# 3-pin-radio-programmer.net
KiCad netlist of a schematic drawn in EAGLE
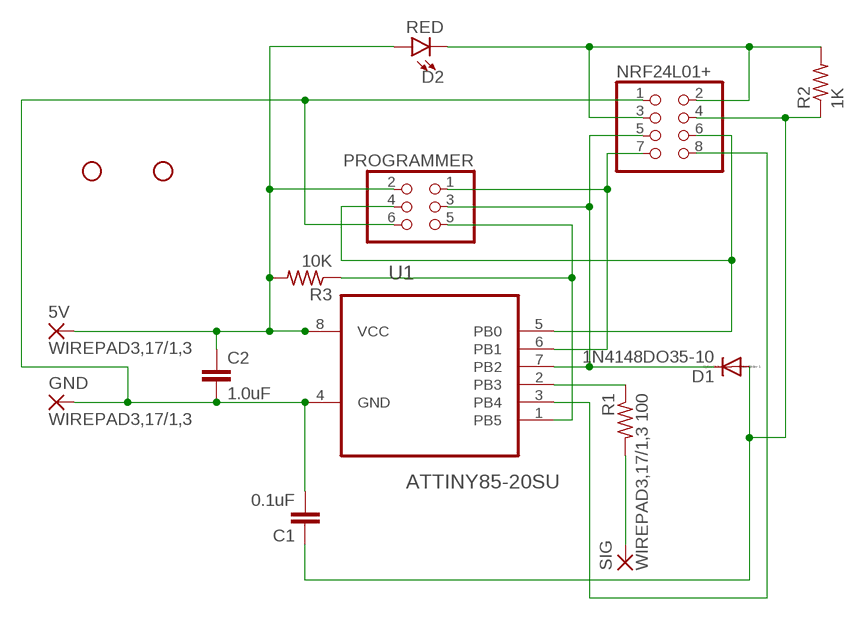
[diagram p0: schematic, sheet 1]

(export (version "E")
  (design (tool "Eeschema 10.0.6"))
  (components
    (comp (ref "5V")
      (value "WIREPAD3,17/1,3")
      (footprint "eagle-import:3,17_1,3")
      (libsource (lib "eagle-import") (part "WIREPAD3,17/1,3"))
    )
    (comp (ref "C1")
      (value "0.1uF")
      (footprint "eagle-import:0603")
      (libsource (lib "eagle-import") (part "0.1UF-0603-25V-5%"))
    )
    (comp (ref "C2")
      (value "1.0uF")
      (footprint "eagle-import:0603")
      (libsource (lib "eagle-import") (part "1.0UF-0603-16V-10%"))
    )
    (comp (ref "D1")
      (value "1N4148DO35-10")
      (footprint "eagle-import:DO35-10")
      (libsource (lib "eagle-import") (part "1N4148DO35-10"))
    )
    (comp (ref "D2")
      (value "RED")
      (footprint "eagle-import:LED_3MM")
      (libsource (lib "eagle-import") (part "LED3MM"))
    )
    (comp (ref "GND")
      (value "WIREPAD3,17/1,3")
      (footprint "eagle-import:3,17_1,3")
      (libsource (lib "eagle-import") (part "WIREPAD3,17/1,3"))
    )
    (comp (ref "H1")
      (value "STAND-OFF")
      (footprint "eagle-import:STAND-OFF")
      (libsource (lib "eagle-import") (part "STAND-OFF"))
    )
    (comp (ref "H2")
      (value "STAND-OFF")
      (footprint "eagle-import:STAND-OFF")
      (libsource (lib "eagle-import") (part "STAND-OFF"))
    )
    (comp (ref "NRF24L01+")
      (value "PINHD-2X4")
      (footprint "eagle-import:2X04")
      (libsource (lib "eagle-import") (part "PINHD-2X4"))
    )
    (comp (ref "PROGRAMMER")
      (value "PINHD-2X3")
      (footprint "eagle-import:2X03")
      (libsource (lib "eagle-import") (part "PINHD-2X3"))
    )
    (comp (ref "R1")
      (value "100")
      (footprint "eagle-import:R0805")
      (libsource (lib "eagle-import") (part "R-US_R0805"))
    )
    (comp (ref "R2")
      (value "1K")
      (footprint "eagle-import:R0805")
      (libsource (lib "eagle-import") (part "R-US_R0805"))
    )
    (comp (ref "R3")
      (value "10K")
      (footprint "eagle-import:R0805")
      (libsource (lib "eagle-import") (part "R-US_R0805"))
    )
    (comp (ref "SIG")
      (value "WIREPAD3,17/1,3")
      (footprint "eagle-import:3,17_1,3")
      (libsource (lib "eagle-import") (part "WIREPAD3,17/1,3"))
    )
    (comp (ref "U1")
      (value "ATTINY85-20SU")
      (footprint "eagle-import:SOIC127P798X216-8N")
      (libsource (lib "eagle-import") (part "ATTINY85-20SU"))
    )
  )
  (nets
    (net (code "1") (name "Net-(5V-P)") (class "Default")
      (node (ref "5V") (pin "1") (pinfunction "P_1") (pintype "passive"))
      (node (ref "C2") (pin "1") (pinfunction "1_1") (pintype "passive"))
      (node (ref "D2") (pin "A") (pinfunction "A_A") (pintype "passive"))
      (node (ref "PROGRAMMER") (pin "2") (pinfunction "2_2") (pintype "passive"))
      (node (ref "R3") (pin "2") (pinfunction "2_2") (pintype "passive"))
      (node (ref "U1") (pin "8") (pinfunction "VCC_8") (pintype "power_in"))
    )
    (net (code "2") (name "Net-(C1-Pad1)") (class "Default")
      (node (ref "C1") (pin "1") (pinfunction "1_1") (pintype "passive"))
      (node (ref "D1") (pin "A") (pinfunction "A_A") (pintype "passive"))
      (node (ref "NRF24L01+") (pin "4") (pinfunction "4_4") (pintype "passive"))
      (node (ref "R2") (pin "1") (pinfunction "1_1") (pintype "passive"))
    )
    (net (code "3") (name "Net-(D2-C)") (class "Default")
      (node (ref "D2") (pin "K") (pinfunction "C_K") (pintype "passive"))
      (node (ref "NRF24L01+") (pin "2") (pinfunction "2_2") (pintype "passive"))
      (node (ref "NRF24L01+") (pin "3") (pinfunction "3_3") (pintype "passive"))
      (node (ref "R2") (pin "2") (pinfunction "2_2") (pintype "passive"))
    )
    (net (code "4") (name "Net-(GND-P)") (class "Default")
      (node (ref "C1") (pin "2") (pinfunction "2_2") (pintype "passive"))
      (node (ref "C2") (pin "2") (pinfunction "2_2") (pintype "passive"))
      (node (ref "GND") (pin "1") (pinfunction "P_1") (pintype "passive"))
      (node (ref "NRF24L01+") (pin "1") (pinfunction "1_1") (pintype "passive"))
      (node (ref "PROGRAMMER") (pin "6") (pinfunction "6_6") (pintype "passive"))
      (node (ref "U1") (pin "4") (pinfunction "GND_4") (pintype "passive"))
    )
    (net (code "5") (name "Net-(SIG-P)") (class "Default")
      (node (ref "R1") (pin "2") (pinfunction "2_2") (pintype "passive"))
      (node (ref "SIG") (pin "1") (pinfunction "P_1") (pintype "passive"))
    )
    (net (code "6") (name "Net-(U1-PB0)") (class "Default")
      (node (ref "NRF24L01+") (pin "6") (pinfunction "6_6") (pintype "passive"))
      (node (ref "PROGRAMMER") (pin "4") (pinfunction "4_4") (pintype "passive"))
      (node (ref "U1") (pin "5") (pinfunction "PB0_5") (pintype "bidirectional"))
    )
    (net (code "7") (name "Net-(U1-PB1)") (class "Default")
      (node (ref "NRF24L01+") (pin "7") (pinfunction "7_7") (pintype "passive"))
      (node (ref "PROGRAMMER") (pin "1") (pinfunction "1_1") (pintype "passive"))
      (node (ref "U1") (pin "6") (pinfunction "PB1_6") (pintype "bidirectional"))
    )
    (net (code "8") (name "Net-(U1-PB2)") (class "Default")
      (node (ref "D1") (pin "C") (pinfunction "C_C") (pintype "passive"))
      (node (ref "NRF24L01+") (pin "5") (pinfunction "5_5") (pintype "passive"))
      (node (ref "PROGRAMMER") (pin "3") (pinfunction "3_3") (pintype "passive"))
      (node (ref "U1") (pin "7") (pinfunction "PB2_7") (pintype "bidirectional"))
    )
    (net (code "9") (name "Net-(U1-PB3)") (class "Default")
      (node (ref "R1") (pin "1") (pinfunction "1_1") (pintype "passive"))
      (node (ref "U1") (pin "2") (pinfunction "PB3_2") (pintype "bidirectional"))
    )
    (net (code "10") (name "Net-(U1-PB4)") (class "Default")
      (node (ref "NRF24L01+") (pin "8") (pinfunction "8_8") (pintype "passive"))
      (node (ref "U1") (pin "3") (pinfunction "PB4_3") (pintype "bidirectional"))
    )
    (net (code "11") (name "Net-(U1-PB5)") (class "Default")
      (node (ref "PROGRAMMER") (pin "5") (pinfunction "5_5") (pintype "passive"))
      (node (ref "R3") (pin "1") (pinfunction "1_1") (pintype "passive"))
      (node (ref "U1") (pin "1") (pinfunction "PB5_1") (pintype "bidirectional"))
    )
  )
)
